# gxb172-opamp-mk-1_0_0.net
KiCad netlist of a schematic drawn in EAGLE
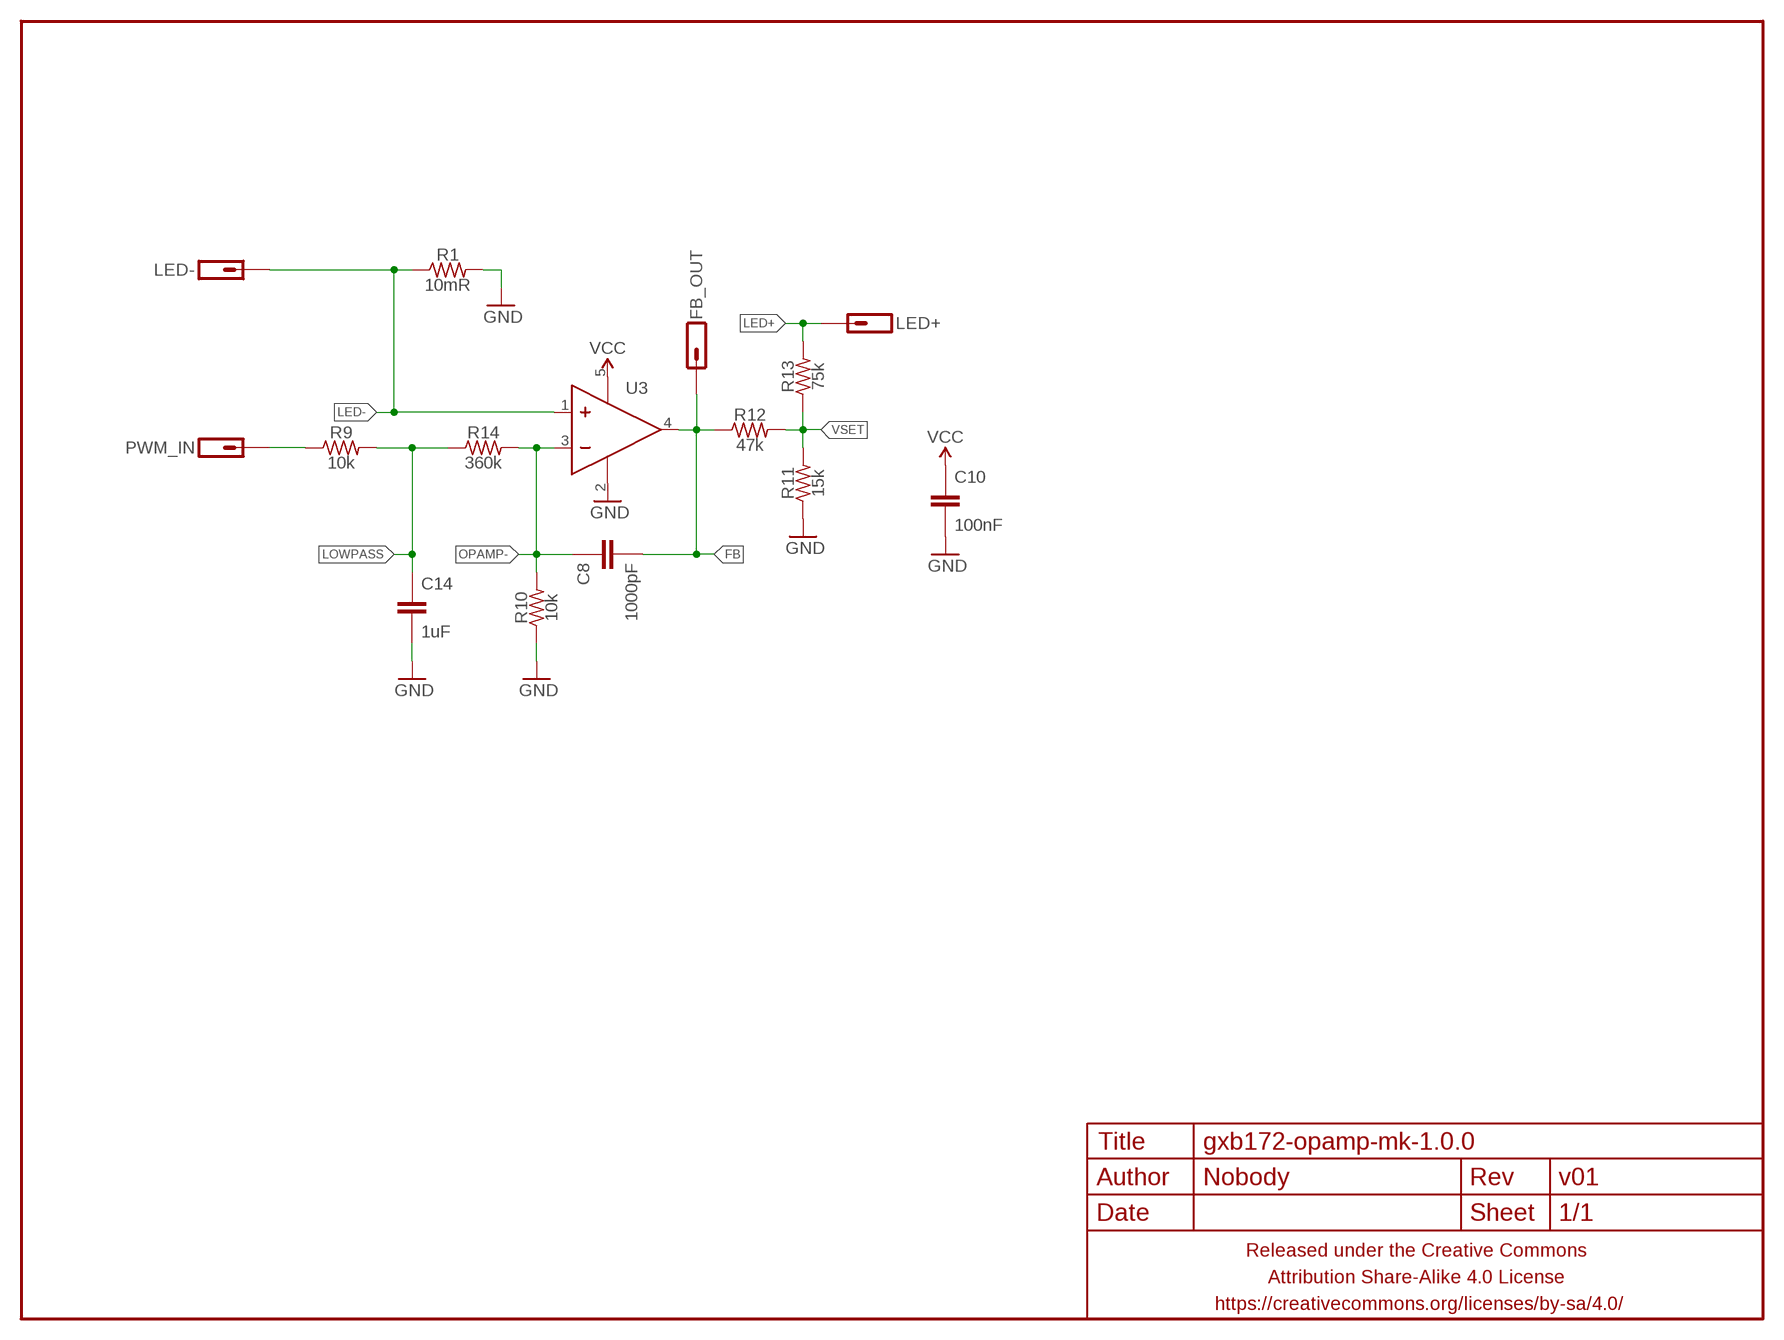
[diagram p0: schematic, sheet 1]

(export (version "E")
  (design (tool "Eeschema 10.0.6"))
  (components
    (comp (ref "C8")
      (value "1000pF")
      (footprint "eagle-import:C0402")
      (libsource (lib "eagle-import") (part "CAPACITOR-CERAMICC0402"))
    )
    (comp (ref "C10")
      (value "100nF")
      (footprint "eagle-import:C0402")
      (libsource (lib "eagle-import") (part "CAPACITOR-CERAMICC0402"))
    )
    (comp (ref "C14")
      (value "1uF")
      (footprint "eagle-import:C0402")
      (libsource (lib "eagle-import") (part "CAPACITOR-CERAMICC0402"))
    )
    (comp (ref "FB_OUT")
      (value "M01PTH")
      (footprint "eagle-import:1X01")
      (libsource (lib "eagle-import") (part "M01PTH"))
    )
    (comp (ref "FRAME1")
      (value "FRAME-LETTERNO_PACKAGE")
      (footprint "eagle-import:DUMMY")
      (fields (field (name "DESIGNER") "Nobody") (field (name "VERSION") "v01"))
      (libsource (lib "eagle-import") (part "FRAME-LETTERNO_PACKAGE"))
    )
    (comp (ref "LED+")
      (value "M01PTH")
      (footprint "eagle-import:1X01")
      (libsource (lib "eagle-import") (part "M01PTH"))
    )
    (comp (ref "LED-")
      (value "M01PTH")
      (footprint "eagle-import:1X01")
      (libsource (lib "eagle-import") (part "M01PTH"))
    )
    (comp (ref "PWM_IN")
      (value "M01PTH")
      (footprint "eagle-import:1X01")
      (libsource (lib "eagle-import") (part "M01PTH"))
    )
    (comp (ref "R1")
      (value "10mR")
      (footprint "eagle-import:R0805-TIGHTER")
      (libsource (lib "eagle-import") (part "RESISTORR0805-TIGHTER"))
    )
    (comp (ref "R9")
      (value "10k")
      (footprint "eagle-import:R0402")
      (libsource (lib "eagle-import") (part "RESISTORR0402"))
    )
    (comp (ref "R10")
      (value "10k")
      (footprint "eagle-import:R0402")
      (libsource (lib "eagle-import") (part "RESISTORR0402"))
    )
    (comp (ref "R11")
      (value "15k")
      (footprint "eagle-import:R0402")
      (libsource (lib "eagle-import") (part "RESISTORR0402"))
    )
    (comp (ref "R12")
      (value "47k")
      (footprint "eagle-import:R0402")
      (libsource (lib "eagle-import") (part "RESISTORR0402"))
    )
    (comp (ref "R13")
      (value "75k")
      (footprint "eagle-import:R0402")
      (libsource (lib "eagle-import") (part "RESISTORR0402"))
    )
    (comp (ref "R14")
      (value "360k")
      (footprint "eagle-import:R0402")
      (libsource (lib "eagle-import") (part "RESISTORR0402"))
    )
    (comp (ref "U3")
      (value "OPAMPOPA333-SC-70")
      (footprint "eagle-import:SC70")
      (libsource (lib "eagle-import") (part "OPAMPOPA333-SC-70"))
    )
  )
  (nets
    (net (code "1") (name "FB") (class "Default")
      (node (ref "C8") (pin "2") (pinfunction "2_2") (pintype "passive"))
      (node (ref "FB_OUT") (pin "1") (pinfunction "1_1") (pintype "passive"))
      (node (ref "R12") (pin "1") (pinfunction "1_1") (pintype "passive"))
      (node (ref "U3") (pin "4") (pinfunction "OUT_4") (pintype "output"))
    )
    (net (code "2") (name "GND") (class "Default")
      (node (ref "C10") (pin "2") (pinfunction "2_2") (pintype "passive"))
      (node (ref "C14") (pin "2") (pinfunction "2_2") (pintype "passive"))
      (node (ref "R1") (pin "2") (pinfunction "2_2") (pintype "passive"))
      (node (ref "R10") (pin "1") (pinfunction "1_1") (pintype "passive"))
      (node (ref "R11") (pin "1") (pinfunction "1_1") (pintype "passive"))
      (node (ref "U3") (pin "2") (pinfunction "V-_2") (pintype "power_in"))
    )
    (net (code "3") (name "LED+") (class "Default")
      (node (ref "LED+") (pin "1") (pinfunction "1_1") (pintype "passive"))
      (node (ref "R13") (pin "2") (pinfunction "2_2") (pintype "passive"))
    )
    (net (code "4") (name "LED-") (class "Default")
      (node (ref "LED-") (pin "1") (pinfunction "1_1") (pintype "passive"))
      (node (ref "R1") (pin "1") (pinfunction "1_1") (pintype "passive"))
      (node (ref "U3") (pin "1") (pinfunction "IN+_1") (pintype "input"))
    )
    (net (code "5") (name "LOWPASS") (class "Default")
      (node (ref "C14") (pin "1") (pinfunction "1_1") (pintype "passive"))
      (node (ref "R14") (pin "1") (pinfunction "1_1") (pintype "passive"))
      (node (ref "R9") (pin "2") (pinfunction "2_2") (pintype "passive"))
    )
    (net (code "6") (name "Net-(PWM_IN-Pad1)") (class "Default")
      (node (ref "PWM_IN") (pin "1") (pinfunction "1_1") (pintype "passive"))
      (node (ref "R9") (pin "1") (pinfunction "1_1") (pintype "passive"))
    )
    (net (code "7") (name "OPAMP-") (class "Default")
      (node (ref "C8") (pin "1") (pinfunction "1_1") (pintype "passive"))
      (node (ref "R10") (pin "2") (pinfunction "2_2") (pintype "passive"))
      (node (ref "R14") (pin "2") (pinfunction "2_2") (pintype "passive"))
      (node (ref "U3") (pin "3") (pinfunction "IN-_3") (pintype "input"))
    )
    (net (code "8") (name "VCC") (class "Default")
      (node (ref "C10") (pin "1") (pinfunction "1_1") (pintype "passive"))
      (node (ref "U3") (pin "5") (pinfunction "V+_5") (pintype "power_in"))
    )
    (net (code "9") (name "VSET") (class "Default")
      (node (ref "R11") (pin "2") (pinfunction "2_2") (pintype "passive"))
      (node (ref "R12") (pin "2") (pinfunction "2_2") (pintype "passive"))
      (node (ref "R13") (pin "1") (pinfunction "1_1") (pintype "passive"))
    )
  )
)
